# MRCS-8xDPDT-Relay_v1_2.net
KiCad netlist of a schematic drawn in EAGLE
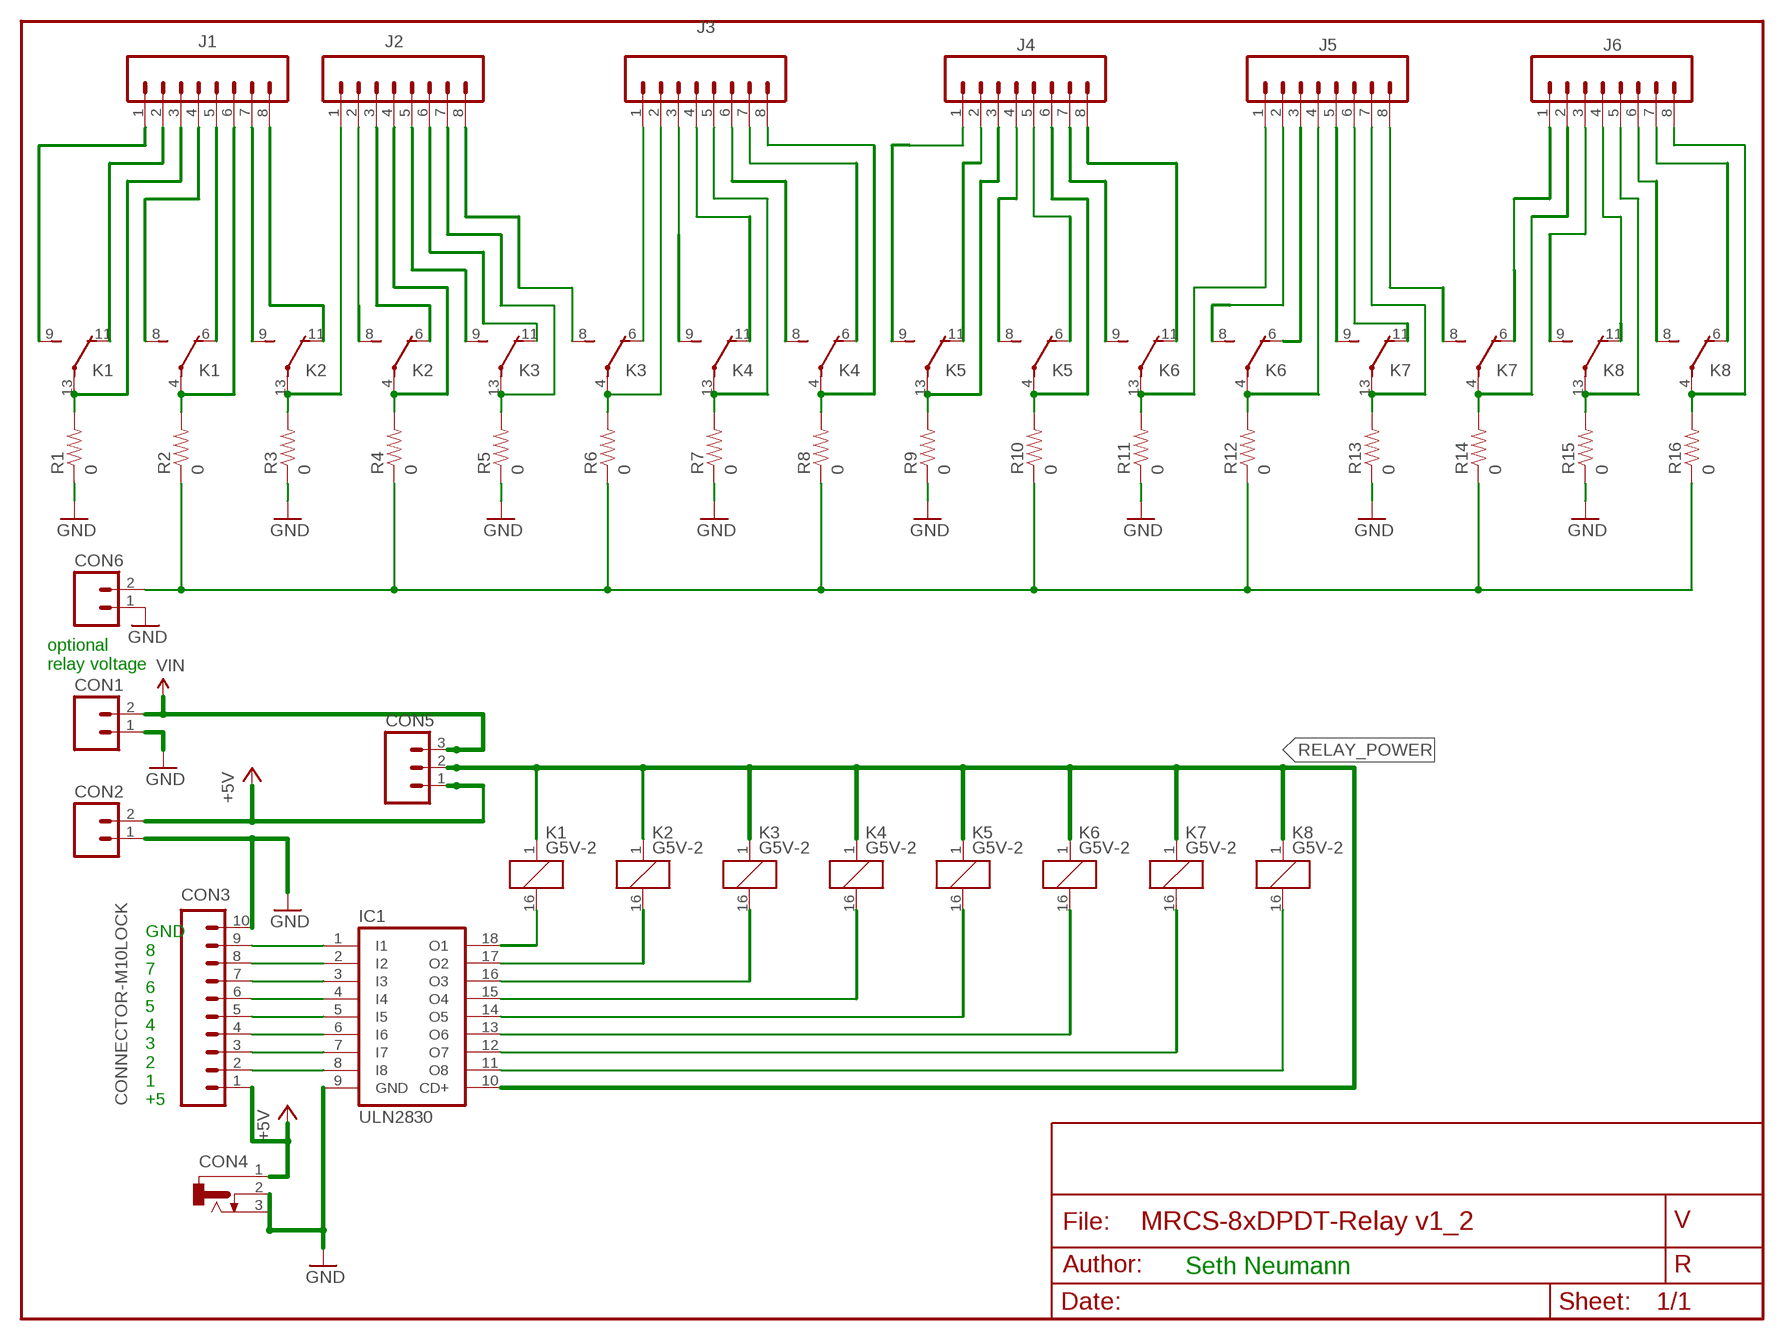
[diagram p0: schematic, sheet 1]

(export (version "E")
  (design (tool "Eeschema 10.0.6"))
  (components
    (comp (ref "CON1")
      (value "CONNECTOR-M023.5MM-LOCK")
      (footprint "eagle-import:SCREWTERMINAL-3.5MM-2_LOCK")
      (libsource (lib "eagle-import") (part "CONNECTOR-M023.5MM-LOCK"))
    )
    (comp (ref "CON2")
      (value "CONNECTOR-M023.5MM-LOCK")
      (footprint "eagle-import:SCREWTERMINAL-3.5MM-2_LOCK")
      (libsource (lib "eagle-import") (part "CONNECTOR-M023.5MM-LOCK"))
    )
    (comp (ref "CON3")
      (value "CONNECTOR-M10LOCK")
      (footprint "eagle-import:1X10_LOCK")
      (libsource (lib "eagle-import") (part "CONNECTOR-M10LOCK"))
    )
    (comp (ref "CON4")
      (value "CONNECTOR-DC-POWER-RA")
      (footprint "eagle-import:DCJ0202")
      (libsource (lib "eagle-import") (part "CONNECTOR-DC-POWER-RA"))
    )
    (comp (ref "CON5")
      (value "CONNECTOR-M03MOLEX-254-LOCK")
      (footprint "eagle-import:MOLEX-1X3_LOCK")
      (libsource (lib "eagle-import") (part "CONNECTOR-M03MOLEX-254-LOCK"))
    )
    (comp (ref "CON6")
      (value "CONNECTOR-M023.5MM-LOCK")
      (footprint "eagle-import:SCREWTERMINAL-3.5MM-2_LOCK")
      (libsource (lib "eagle-import") (part "CONNECTOR-M023.5MM-LOCK"))
    )
    (comp (ref "IC1")
      (value "ULN2830")
      (footprint "eagle-import:DIL18")
      (libsource (lib "eagle-import") (part "ULN2803A"))
    )
    (comp (ref "J1")
      (value "CONNECTOR-M08LOCK")
      (footprint "eagle-import:1X08_LOCK")
      (libsource (lib "eagle-import") (part "CONNECTOR-M08LOCK"))
    )
    (comp (ref "J2")
      (value "CONNECTOR-M08LOCK")
      (footprint "eagle-import:1X08_LOCK")
      (libsource (lib "eagle-import") (part "CONNECTOR-M08LOCK"))
    )
    (comp (ref "J3")
      (value "CONNECTOR-M08LOCK")
      (footprint "eagle-import:1X08_LOCK")
      (libsource (lib "eagle-import") (part "CONNECTOR-M08LOCK"))
    )
    (comp (ref "J4")
      (value "CONNECTOR-M08LOCK")
      (footprint "eagle-import:1X08_LOCK")
      (libsource (lib "eagle-import") (part "CONNECTOR-M08LOCK"))
    )
    (comp (ref "J5")
      (value "CONNECTOR-M08LOCK")
      (footprint "eagle-import:1X08_LOCK")
      (libsource (lib "eagle-import") (part "CONNECTOR-M08LOCK"))
    )
    (comp (ref "J6")
      (value "CONNECTOR-M08LOCK")
      (footprint "eagle-import:1X08_LOCK")
      (libsource (lib "eagle-import") (part "CONNECTOR-M08LOCK"))
    )
    (comp (ref "K1")
      (value "G5V-2")
      (footprint "eagle-import:G5V-2")
      (fields (field (name "MPN") "G5V-2 5DC"))
      (libsource (lib "eagle-import") (part "G5V-2"))
    )
    (comp (ref "K2")
      (value "G5V-2")
      (footprint "eagle-import:G5V-2")
      (fields (field (name "MPN") "G5V-2 5DC"))
      (libsource (lib "eagle-import") (part "G5V-2"))
    )
    (comp (ref "K3")
      (value "G5V-2")
      (footprint "eagle-import:G5V-2")
      (fields (field (name "MPN") "G5V-2 5DC"))
      (libsource (lib "eagle-import") (part "G5V-2"))
    )
    (comp (ref "K4")
      (value "G5V-2")
      (footprint "eagle-import:G5V-2")
      (fields (field (name "MPN") "G5V-2 5DC"))
      (libsource (lib "eagle-import") (part "G5V-2"))
    )
    (comp (ref "K5")
      (value "G5V-2")
      (footprint "eagle-import:G5V-2")
      (fields (field (name "MPN") "G5V-2 5DC"))
      (libsource (lib "eagle-import") (part "G5V-2"))
    )
    (comp (ref "K6")
      (value "G5V-2")
      (footprint "eagle-import:G5V-2")
      (fields (field (name "MPN") "G5V-2 5DC"))
      (libsource (lib "eagle-import") (part "G5V-2"))
    )
    (comp (ref "K7")
      (value "G5V-2")
      (footprint "eagle-import:G5V-2")
      (fields (field (name "MPN") "G5V-2 5DC"))
      (libsource (lib "eagle-import") (part "G5V-2"))
    )
    (comp (ref "K8")
      (value "G5V-2")
      (footprint "eagle-import:G5V-2")
      (fields (field (name "MPN") "G5V-2 5DC"))
      (libsource (lib "eagle-import") (part "G5V-2"))
    )
    (comp (ref "R1")
      (value "0")
      (footprint "eagle-import:CUT-R")
      (libsource (lib "eagle-import") (part "RPTH-R0"))
    )
    (comp (ref "R2")
      (value "0")
      (footprint "eagle-import:CUT-R")
      (libsource (lib "eagle-import") (part "RPTH-R0"))
    )
    (comp (ref "R3")
      (value "0")
      (footprint "eagle-import:CUT-R")
      (libsource (lib "eagle-import") (part "RPTH-R0"))
    )
    (comp (ref "R4")
      (value "0")
      (footprint "eagle-import:CUT-R")
      (libsource (lib "eagle-import") (part "RPTH-R0"))
    )
    (comp (ref "R5")
      (value "0")
      (footprint "eagle-import:CUT-R")
      (libsource (lib "eagle-import") (part "RPTH-R0"))
    )
    (comp (ref "R6")
      (value "0")
      (footprint "eagle-import:CUT-R")
      (libsource (lib "eagle-import") (part "RPTH-R0"))
    )
    (comp (ref "R7")
      (value "0")
      (footprint "eagle-import:CUT-R")
      (libsource (lib "eagle-import") (part "RPTH-R0"))
    )
    (comp (ref "R8")
      (value "0")
      (footprint "eagle-import:CUT-R")
      (libsource (lib "eagle-import") (part "RPTH-R0"))
    )
    (comp (ref "R9")
      (value "0")
      (footprint "eagle-import:CUT-R")
      (libsource (lib "eagle-import") (part "RPTH-R0"))
    )
    (comp (ref "R10")
      (value "0")
      (footprint "eagle-import:CUT-R")
      (libsource (lib "eagle-import") (part "RPTH-R0"))
    )
    (comp (ref "R11")
      (value "0")
      (footprint "eagle-import:CUT-R")
      (libsource (lib "eagle-import") (part "RPTH-R0"))
    )
    (comp (ref "R12")
      (value "0")
      (footprint "eagle-import:CUT-R")
      (libsource (lib "eagle-import") (part "RPTH-R0"))
    )
    (comp (ref "R13")
      (value "0")
      (footprint "eagle-import:CUT-R")
      (libsource (lib "eagle-import") (part "RPTH-R0"))
    )
    (comp (ref "R14")
      (value "0")
      (footprint "eagle-import:CUT-R")
      (libsource (lib "eagle-import") (part "RPTH-R0"))
    )
    (comp (ref "R15")
      (value "0")
      (footprint "eagle-import:CUT-R")
      (libsource (lib "eagle-import") (part "RPTH-R0"))
    )
    (comp (ref "R16")
      (value "0")
      (footprint "eagle-import:CUT-R")
      (libsource (lib "eagle-import") (part "RPTH-R0"))
    )
  )
  (nets
    (net (code "1") (name "+5V") (class "Default")
      (node (ref "CON2") (pin "2") (pinfunction "B_2") (pintype "passive"))
      (node (ref "CON3") (pin "1") (pinfunction "1_1") (pintype "passive"))
      (node (ref "CON4") (pin "1") (pinfunction "1_1") (pintype "passive"))
      (node (ref "CON5") (pin "1") (pinfunction "1_1") (pintype "passive"))
    )
    (net (code "2") (name "GND") (class "Default")
      (node (ref "CON1") (pin "1") (pinfunction "A_1") (pintype "passive"))
      (node (ref "CON2") (pin "1") (pinfunction "A_1") (pintype "passive"))
      (node (ref "CON3") (pin "10") (pinfunction "10_10") (pintype "passive"))
      (node (ref "CON4") (pin "2") (pinfunction "2_2") (pintype "passive"))
      (node (ref "CON4") (pin "3") (pinfunction "3_3") (pintype "passive"))
      (node (ref "CON6") (pin "1") (pinfunction "A_1") (pintype "passive"))
      (node (ref "IC1") (pin "9") (pinfunction "GND_9") (pintype "power_in"))
      (node (ref "R1") (pin "P2") (pinfunction "1_P2") (pintype "passive"))
      (node (ref "R11") (pin "P2") (pinfunction "1_P2") (pintype "passive"))
      (node (ref "R13") (pin "P2") (pinfunction "1_P2") (pintype "passive"))
      (node (ref "R15") (pin "P2") (pinfunction "1_P2") (pintype "passive"))
      (node (ref "R3") (pin "P2") (pinfunction "1_P2") (pintype "passive"))
      (node (ref "R5") (pin "P2") (pinfunction "1_P2") (pintype "passive"))
      (node (ref "R7") (pin "P2") (pinfunction "1_P2") (pintype "passive"))
      (node (ref "R9") (pin "P2") (pinfunction "1_P2") (pintype "passive"))
    )
    (net (code "3") (name "Net-(CON6-B)") (class "Default")
      (node (ref "CON6") (pin "2") (pinfunction "B_2") (pintype "passive"))
      (node (ref "R10") (pin "P2") (pinfunction "1_P2") (pintype "passive"))
      (node (ref "R12") (pin "P2") (pinfunction "1_P2") (pintype "passive"))
      (node (ref "R14") (pin "P2") (pinfunction "1_P2") (pintype "passive"))
      (node (ref "R16") (pin "P2") (pinfunction "1_P2") (pintype "passive"))
      (node (ref "R2") (pin "P2") (pinfunction "1_P2") (pintype "passive"))
      (node (ref "R4") (pin "P2") (pinfunction "1_P2") (pintype "passive"))
      (node (ref "R6") (pin "P2") (pinfunction "1_P2") (pintype "passive"))
      (node (ref "R8") (pin "P2") (pinfunction "1_P2") (pintype "passive"))
    )
    (net (code "4") (name "Net-(IC1-I1)") (class "Default")
      (node (ref "CON3") (pin "9") (pinfunction "9_9") (pintype "passive"))
      (node (ref "IC1") (pin "1") (pinfunction "I1_1") (pintype "input"))
    )
    (net (code "5") (name "Net-(IC1-I2)") (class "Default")
      (node (ref "CON3") (pin "8") (pinfunction "8_8") (pintype "passive"))
      (node (ref "IC1") (pin "2") (pinfunction "I2_2") (pintype "input"))
    )
    (net (code "6") (name "Net-(IC1-I3)") (class "Default")
      (node (ref "CON3") (pin "7") (pinfunction "7_7") (pintype "passive"))
      (node (ref "IC1") (pin "3") (pinfunction "I3_3") (pintype "input"))
    )
    (net (code "7") (name "Net-(IC1-I4)") (class "Default")
      (node (ref "CON3") (pin "6") (pinfunction "6_6") (pintype "passive"))
      (node (ref "IC1") (pin "4") (pinfunction "I4_4") (pintype "input"))
    )
    (net (code "8") (name "Net-(IC1-I5)") (class "Default")
      (node (ref "CON3") (pin "5") (pinfunction "5_5") (pintype "passive"))
      (node (ref "IC1") (pin "5") (pinfunction "I5_5") (pintype "input"))
    )
    (net (code "9") (name "Net-(IC1-I6)") (class "Default")
      (node (ref "CON3") (pin "4") (pinfunction "4_4") (pintype "passive"))
      (node (ref "IC1") (pin "6") (pinfunction "I6_6") (pintype "input"))
    )
    (net (code "10") (name "Net-(IC1-I7)") (class "Default")
      (node (ref "CON3") (pin "3") (pinfunction "3_3") (pintype "passive"))
      (node (ref "IC1") (pin "7") (pinfunction "I7_7") (pintype "input"))
    )
    (net (code "11") (name "Net-(IC1-I8)") (class "Default")
      (node (ref "CON3") (pin "2") (pinfunction "2_2") (pintype "passive"))
      (node (ref "IC1") (pin "8") (pinfunction "I8_8") (pintype "input"))
    )
    (net (code "12") (name "Net-(IC1-O1)") (class "Default")
      (node (ref "IC1") (pin "18") (pinfunction "O1_18") (pintype "open_collector"))
      (node (ref "K1") (pin "16") (pinfunction "2_16") (pintype "passive"))
    )
    (net (code "13") (name "Net-(IC1-O2)") (class "Default")
      (node (ref "IC1") (pin "17") (pinfunction "O2_17") (pintype "open_collector"))
      (node (ref "K2") (pin "16") (pinfunction "2_16") (pintype "passive"))
    )
    (net (code "14") (name "Net-(IC1-O3)") (class "Default")
      (node (ref "IC1") (pin "16") (pinfunction "O3_16") (pintype "open_collector"))
      (node (ref "K3") (pin "16") (pinfunction "2_16") (pintype "passive"))
    )
    (net (code "15") (name "Net-(IC1-O4)") (class "Default")
      (node (ref "IC1") (pin "15") (pinfunction "O4_15") (pintype "open_collector"))
      (node (ref "K4") (pin "16") (pinfunction "2_16") (pintype "passive"))
    )
    (net (code "16") (name "Net-(IC1-O5)") (class "Default")
      (node (ref "IC1") (pin "14") (pinfunction "O5_14") (pintype "open_collector"))
      (node (ref "K5") (pin "16") (pinfunction "2_16") (pintype "passive"))
    )
    (net (code "17") (name "Net-(IC1-O6)") (class "Default")
      (node (ref "IC1") (pin "13") (pinfunction "O6_13") (pintype "open_collector"))
      (node (ref "K6") (pin "16") (pinfunction "2_16") (pintype "passive"))
    )
    (net (code "18") (name "Net-(IC1-O7)") (class "Default")
      (node (ref "IC1") (pin "12") (pinfunction "O7_12") (pintype "open_collector"))
      (node (ref "K7") (pin "16") (pinfunction "2_16") (pintype "passive"))
    )
    (net (code "19") (name "Net-(IC1-O8)") (class "Default")
      (node (ref "IC1") (pin "11") (pinfunction "O8_11") (pintype "open_collector"))
      (node (ref "K8") (pin "16") (pinfunction "2_16") (pintype "passive"))
    )
    (net (code "20") (name "Net-(K1A-O)") (class "Default")
      (node (ref "J1") (pin "5") (pinfunction "5_5") (pintype "passive"))
      (node (ref "K1") (pin "6") (pinfunction "O_6") (pintype "passive"))
    )
    (net (code "21") (name "Net-(K1A-P)") (class "Default")
      (node (ref "J1") (pin "6") (pinfunction "6_6") (pintype "passive"))
      (node (ref "K1") (pin "4") (pinfunction "P_4") (pintype "passive"))
      (node (ref "R2") (pin "P1") (pinfunction "2_P1") (pintype "passive"))
    )
    (net (code "22") (name "Net-(K1A-S)") (class "Default")
      (node (ref "J1") (pin "4") (pinfunction "4_4") (pintype "passive"))
      (node (ref "K1") (pin "8") (pinfunction "S_8") (pintype "passive"))
    )
    (net (code "23") (name "Net-(K1B-O)") (class "Default")
      (node (ref "J1") (pin "2") (pinfunction "2_2") (pintype "passive"))
      (node (ref "K1") (pin "11") (pinfunction "O_11") (pintype "passive"))
    )
    (net (code "24") (name "Net-(K1B-P)") (class "Default")
      (node (ref "J1") (pin "3") (pinfunction "3_3") (pintype "passive"))
      (node (ref "K1") (pin "13") (pinfunction "P_13") (pintype "passive"))
      (node (ref "R1") (pin "P1") (pinfunction "2_P1") (pintype "passive"))
    )
    (net (code "25") (name "Net-(K1B-S)") (class "Default")
      (node (ref "J1") (pin "1") (pinfunction "1_1") (pintype "passive"))
      (node (ref "K1") (pin "9") (pinfunction "S_9") (pintype "passive"))
    )
    (net (code "26") (name "Net-(K2A-O)") (class "Default")
      (node (ref "J2") (pin "3") (pinfunction "3_3") (pintype "passive"))
      (node (ref "K2") (pin "6") (pinfunction "O_6") (pintype "passive"))
    )
    (net (code "27") (name "Net-(K2A-P)") (class "Default")
      (node (ref "J2") (pin "4") (pinfunction "4_4") (pintype "passive"))
      (node (ref "K2") (pin "4") (pinfunction "P_4") (pintype "passive"))
      (node (ref "R4") (pin "P1") (pinfunction "2_P1") (pintype "passive"))
    )
    (net (code "28") (name "Net-(K2A-S)") (class "Default")
      (node (ref "J2") (pin "2") (pinfunction "2_2") (pintype "passive"))
      (node (ref "K2") (pin "8") (pinfunction "S_8") (pintype "passive"))
    )
    (net (code "29") (name "Net-(K2B-O)") (class "Default")
      (node (ref "J1") (pin "8") (pinfunction "8_8") (pintype "passive"))
      (node (ref "K2") (pin "11") (pinfunction "O_11") (pintype "passive"))
    )
    (net (code "30") (name "Net-(K2B-P)") (class "Default")
      (node (ref "J2") (pin "1") (pinfunction "1_1") (pintype "passive"))
      (node (ref "K2") (pin "13") (pinfunction "P_13") (pintype "passive"))
      (node (ref "R3") (pin "P1") (pinfunction "2_P1") (pintype "passive"))
    )
    (net (code "31") (name "Net-(K2B-S)") (class "Default")
      (node (ref "J1") (pin "7") (pinfunction "7_7") (pintype "passive"))
      (node (ref "K2") (pin "9") (pinfunction "S_9") (pintype "passive"))
    )
    (net (code "32") (name "Net-(K3A-O)") (class "Default")
      (node (ref "J3") (pin "1") (pinfunction "1_1") (pintype "passive"))
      (node (ref "K3") (pin "6") (pinfunction "O_6") (pintype "passive"))
    )
    (net (code "33") (name "Net-(K3A-P)") (class "Default")
      (node (ref "J3") (pin "2") (pinfunction "2_2") (pintype "passive"))
      (node (ref "K3") (pin "4") (pinfunction "P_4") (pintype "passive"))
      (node (ref "R6") (pin "P1") (pinfunction "2_P1") (pintype "passive"))
    )
    (net (code "34") (name "Net-(K3A-S)") (class "Default")
      (node (ref "J2") (pin "8") (pinfunction "8_8") (pintype "passive"))
      (node (ref "K3") (pin "8") (pinfunction "S_8") (pintype "passive"))
    )
    (net (code "35") (name "Net-(K3B-O)") (class "Default")
      (node (ref "J2") (pin "6") (pinfunction "6_6") (pintype "passive"))
      (node (ref "K3") (pin "11") (pinfunction "O_11") (pintype "passive"))
    )
    (net (code "36") (name "Net-(K3B-P)") (class "Default")
      (node (ref "J2") (pin "7") (pinfunction "7_7") (pintype "passive"))
      (node (ref "K3") (pin "13") (pinfunction "P_13") (pintype "passive"))
      (node (ref "R5") (pin "P1") (pinfunction "2_P1") (pintype "passive"))
    )
    (net (code "37") (name "Net-(K3B-S)") (class "Default")
      (node (ref "J2") (pin "5") (pinfunction "5_5") (pintype "passive"))
      (node (ref "K3") (pin "9") (pinfunction "S_9") (pintype "passive"))
    )
    (net (code "38") (name "Net-(K4A-O)") (class "Default")
      (node (ref "J3") (pin "7") (pinfunction "7_7") (pintype "passive"))
      (node (ref "K4") (pin "6") (pinfunction "O_6") (pintype "passive"))
    )
    (net (code "39") (name "Net-(K4A-P)") (class "Default")
      (node (ref "J3") (pin "8") (pinfunction "8_8") (pintype "passive"))
      (node (ref "K4") (pin "4") (pinfunction "P_4") (pintype "passive"))
      (node (ref "R8") (pin "P1") (pinfunction "2_P1") (pintype "passive"))
    )
    (net (code "40") (name "Net-(K4A-S)") (class "Default")
      (node (ref "J3") (pin "6") (pinfunction "6_6") (pintype "passive"))
      (node (ref "K4") (pin "8") (pinfunction "S_8") (pintype "passive"))
    )
    (net (code "41") (name "Net-(K4B-O)") (class "Default")
      (node (ref "J3") (pin "4") (pinfunction "4_4") (pintype "passive"))
      (node (ref "K4") (pin "11") (pinfunction "O_11") (pintype "passive"))
    )
    (net (code "42") (name "Net-(K4B-P)") (class "Default")
      (node (ref "J3") (pin "5") (pinfunction "5_5") (pintype "passive"))
      (node (ref "K4") (pin "13") (pinfunction "P_13") (pintype "passive"))
      (node (ref "R7") (pin "P1") (pinfunction "2_P1") (pintype "passive"))
    )
    (net (code "43") (name "Net-(K4B-S)") (class "Default")
      (node (ref "J3") (pin "3") (pinfunction "3_3") (pintype "passive"))
      (node (ref "K4") (pin "9") (pinfunction "S_9") (pintype "passive"))
    )
    (net (code "44") (name "Net-(K5A-O)") (class "Default")
      (node (ref "J4") (pin "5") (pinfunction "5_5") (pintype "passive"))
      (node (ref "K5") (pin "6") (pinfunction "O_6") (pintype "passive"))
    )
    (net (code "45") (name "Net-(K5A-P)") (class "Default")
      (node (ref "J4") (pin "6") (pinfunction "6_6") (pintype "passive"))
      (node (ref "K5") (pin "4") (pinfunction "P_4") (pintype "passive"))
      (node (ref "R10") (pin "P1") (pinfunction "2_P1") (pintype "passive"))
    )
    (net (code "46") (name "Net-(K5A-S)") (class "Default")
      (node (ref "J4") (pin "4") (pinfunction "4_4") (pintype "passive"))
      (node (ref "K5") (pin "8") (pinfunction "S_8") (pintype "passive"))
    )
    (net (code "47") (name "Net-(K5B-O)") (class "Default")
      (node (ref "J4") (pin "2") (pinfunction "2_2") (pintype "passive"))
      (node (ref "K5") (pin "11") (pinfunction "O_11") (pintype "passive"))
    )
    (net (code "48") (name "Net-(K5B-P)") (class "Default")
      (node (ref "J4") (pin "3") (pinfunction "3_3") (pintype "passive"))
      (node (ref "K5") (pin "13") (pinfunction "P_13") (pintype "passive"))
      (node (ref "R9") (pin "P1") (pinfunction "2_P1") (pintype "passive"))
    )
    (net (code "49") (name "Net-(K5B-S)") (class "Default")
      (node (ref "J4") (pin "1") (pinfunction "1_1") (pintype "passive"))
      (node (ref "K5") (pin "9") (pinfunction "S_9") (pintype "passive"))
    )
    (net (code "50") (name "Net-(K6A-O)") (class "Default")
      (node (ref "J5") (pin "3") (pinfunction "3_3") (pintype "passive"))
      (node (ref "K6") (pin "6") (pinfunction "O_6") (pintype "passive"))
    )
    (net (code "51") (name "Net-(K6A-P)") (class "Default")
      (node (ref "J5") (pin "4") (pinfunction "4_4") (pintype "passive"))
      (node (ref "K6") (pin "4") (pinfunction "P_4") (pintype "passive"))
      (node (ref "R12") (pin "P1") (pinfunction "2_P1") (pintype "passive"))
    )
    (net (code "52") (name "Net-(K6A-S)") (class "Default")
      (node (ref "J5") (pin "2") (pinfunction "2_2") (pintype "passive"))
      (node (ref "K6") (pin "8") (pinfunction "S_8") (pintype "passive"))
    )
    (net (code "53") (name "Net-(K6B-O)") (class "Default")
      (node (ref "J4") (pin "8") (pinfunction "8_8") (pintype "passive"))
      (node (ref "K6") (pin "11") (pinfunction "O_11") (pintype "passive"))
    )
    (net (code "54") (name "Net-(K6B-P)") (class "Default")
      (node (ref "J5") (pin "1") (pinfunction "1_1") (pintype "passive"))
      (node (ref "K6") (pin "13") (pinfunction "P_13") (pintype "passive"))
      (node (ref "R11") (pin "P1") (pinfunction "2_P1") (pintype "passive"))
    )
    (net (code "55") (name "Net-(K6B-S)") (class "Default")
      (node (ref "J4") (pin "7") (pinfunction "7_7") (pintype "passive"))
      (node (ref "K6") (pin "9") (pinfunction "S_9") (pintype "passive"))
    )
    (net (code "56") (name "Net-(K7A-O)") (class "Default")
      (node (ref "J6") (pin "1") (pinfunction "1_1") (pintype "passive"))
      (node (ref "K7") (pin "6") (pinfunction "O_6") (pintype "passive"))
    )
    (net (code "57") (name "Net-(K7A-P)") (class "Default")
      (node (ref "J6") (pin "2") (pinfunction "2_2") (pintype "passive"))
      (node (ref "K7") (pin "4") (pinfunction "P_4") (pintype "passive"))
      (node (ref "R14") (pin "P1") (pinfunction "2_P1") (pintype "passive"))
    )
    (net (code "58") (name "Net-(K7A-S)") (class "Default")
      (node (ref "J5") (pin "8") (pinfunction "8_8") (pintype "passive"))
      (node (ref "K7") (pin "8") (pinfunction "S_8") (pintype "passive"))
    )
    (net (code "59") (name "Net-(K7B-O)") (class "Default")
      (node (ref "J5") (pin "6") (pinfunction "6_6") (pintype "passive"))
      (node (ref "K7") (pin "11") (pinfunction "O_11") (pintype "passive"))
    )
    (net (code "60") (name "Net-(K7B-P)") (class "Default")
      (node (ref "J5") (pin "7") (pinfunction "7_7") (pintype "passive"))
      (node (ref "K7") (pin "13") (pinfunction "P_13") (pintype "passive"))
      (node (ref "R13") (pin "P1") (pinfunction "2_P1") (pintype "passive"))
    )
    (net (code "61") (name "Net-(K7B-S)") (class "Default")
      (node (ref "J5") (pin "5") (pinfunction "5_5") (pintype "passive"))
      (node (ref "K7") (pin "9") (pinfunction "S_9") (pintype "passive"))
    )
    (net (code "62") (name "Net-(K8A-O)") (class "Default")
      (node (ref "J6") (pin "7") (pinfunction "7_7") (pintype "passive"))
      (node (ref "K8") (pin "6") (pinfunction "O_6") (pintype "passive"))
    )
    (net (code "63") (name "Net-(K8A-P)") (class "Default")
      (node (ref "J6") (pin "8") (pinfunction "8_8") (pintype "passive"))
      (node (ref "K8") (pin "4") (pinfunction "P_4") (pintype "passive"))
      (node (ref "R16") (pin "P1") (pinfunction "2_P1") (pintype "passive"))
    )
    (net (code "64") (name "Net-(K8A-S)") (class "Default")
      (node (ref "J6") (pin "6") (pinfunction "6_6") (pintype "passive"))
      (node (ref "K8") (pin "8") (pinfunction "S_8") (pintype "passive"))
    )
    (net (code "65") (name "Net-(K8B-O)") (class "Default")
      (node (ref "J6") (pin "4") (pinfunction "4_4") (pintype "passive"))
      (node (ref "K8") (pin "11") (pinfunction "O_11") (pintype "passive"))
    )
    (net (code "66") (name "Net-(K8B-P)") (class "Default")
      (node (ref "J6") (pin "5") (pinfunction "5_5") (pintype "passive"))
      (node (ref "K8") (pin "13") (pinfunction "P_13") (pintype "passive"))
      (node (ref "R15") (pin "P1") (pinfunction "2_P1") (pintype "passive"))
    )
    (net (code "67") (name "Net-(K8B-S)") (class "Default")
      (node (ref "J6") (pin "3") (pinfunction "3_3") (pintype "passive"))
      (node (ref "K8") (pin "9") (pinfunction "S_9") (pintype "passive"))
    )
    (net (code "68") (name "RELAY_POWER") (class "Default")
      (node (ref "CON5") (pin "2") (pinfunction "2_2") (pintype "passive"))
      (node (ref "IC1") (pin "10") (pinfunction "CD+_10") (pintype "passive"))
      (node (ref "K1") (pin "1") (pinfunction "1_1") (pintype "passive"))
      (node (ref "K2") (pin "1") (pinfunction "1_1") (pintype "passive"))
      (node (ref "K3") (pin "1") (pinfunction "1_1") (pintype "passive"))
      (node (ref "K4") (pin "1") (pinfunction "1_1") (pintype "passive"))
      (node (ref "K5") (pin "1") (pinfunction "1_1") (pintype "passive"))
      (node (ref "K6") (pin "1") (pinfunction "1_1") (pintype "passive"))
      (node (ref "K7") (pin "1") (pinfunction "1_1") (pintype "passive"))
      (node (ref "K8") (pin "1") (pinfunction "1_1") (pintype "passive"))
    )
    (net (code "69") (name "VIN") (class "Default")
      (node (ref "CON1") (pin "2") (pinfunction "B_2") (pintype "passive"))
      (node (ref "CON5") (pin "3") (pinfunction "3_3") (pintype "passive"))
    )
  )
)
